# CW308_Mechanical.net
KiCad netlist of a schematic drawn in Altium Designer
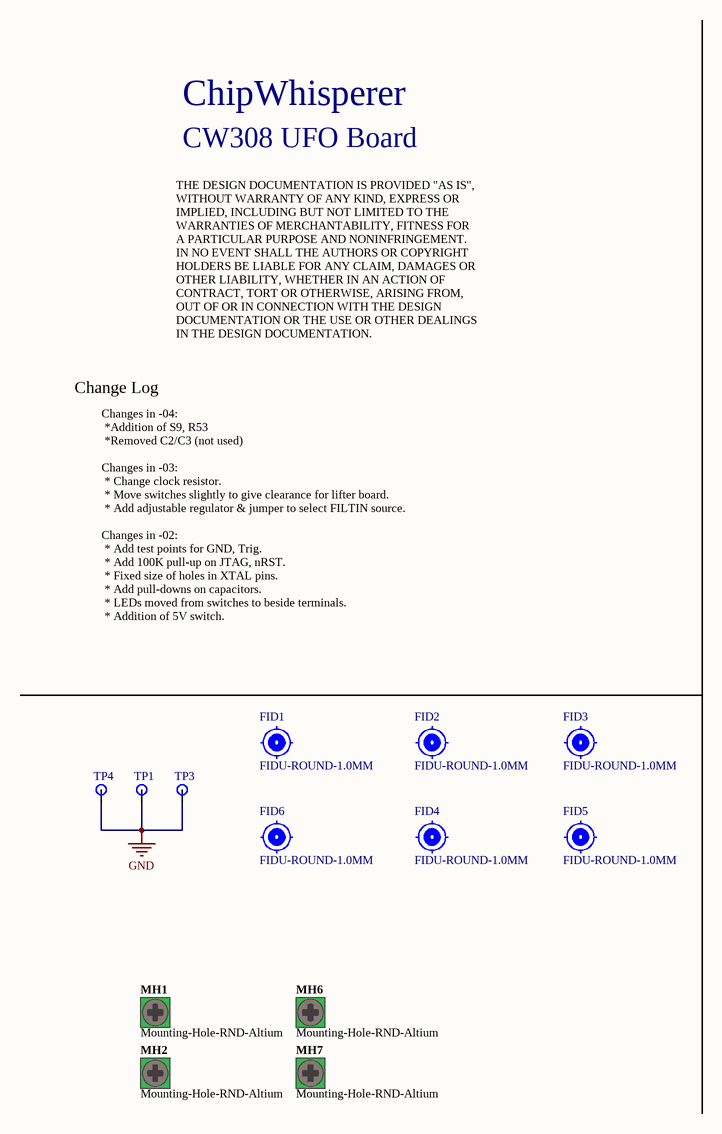
[diagram p0: CW308_Mechanical.SchDoc]

(export (version "E")
  (design (tool "Eeschema 10.0.6"))
  (components
    (comp (ref "FID1")
      (value "FIDU-ROUND-1.0MM")
      (footprint "FIDU-ROUND-1.0mm")
      (description "ROUND FIDUCIAL")
      (libsource (lib "NewAE_AltiumLib") (part "FIDU-ROUND-1.0MM"))
    )
    (comp (ref "FID2")
      (value "FIDU-ROUND-1.0MM")
      (footprint "FIDU-ROUND-1.0mm")
      (description "ROUND FIDUCIAL")
      (libsource (lib "NewAE_AltiumLib") (part "FIDU-ROUND-1.0MM"))
    )
    (comp (ref "FID3")
      (value "FIDU-ROUND-1.0MM")
      (footprint "FIDU-ROUND-1.0mm")
      (description "ROUND FIDUCIAL")
      (libsource (lib "NewAE_AltiumLib") (part "FIDU-ROUND-1.0MM"))
    )
    (comp (ref "FID4")
      (value "FIDU-ROUND-1.0MM")
      (footprint "FIDU-ROUND-1.0mm")
      (description "ROUND FIDUCIAL")
      (libsource (lib "NewAE_AltiumLib") (part "FIDU-ROUND-1.0MM"))
    )
    (comp (ref "FID5")
      (value "FIDU-ROUND-1.0MM")
      (footprint "FIDU-ROUND-1.0mm")
      (description "ROUND FIDUCIAL")
      (libsource (lib "NewAE_AltiumLib") (part "FIDU-ROUND-1.0MM"))
    )
    (comp (ref "FID6")
      (value "FIDU-ROUND-1.0MM")
      (footprint "FIDU-ROUND-1.0mm")
      (description "ROUND FIDUCIAL")
      (libsource (lib "NewAE_AltiumLib") (part "FIDU-ROUND-1.0MM"))
    )
    (comp (ref "MH1")
      (value "Mounting-Hole-RND-Altium")
      (footprint "Mounting-Hole-RND-Altium")
      (description "Mounting Hole, Altium, 4.4mm pad, 3.4mm plated hole")
      (fields (field (name "PUBLISHER") "Altium"))
      (libsource (lib "Altium Content Vault") (part "CMP-0001-00029-1"))
    )
    (comp (ref "MH2")
      (value "Mounting-Hole-RND-Altium")
      (footprint "Mounting-Hole-RND-Altium")
      (description "Mounting Hole, Altium, 4.4mm pad, 3.4mm plated hole")
      (fields (field (name "PUBLISHER") "Altium"))
      (libsource (lib "Altium Content Vault") (part "CMP-0001-00029-1"))
    )
    (comp (ref "MH6")
      (value "Mounting-Hole-RND-Altium")
      (footprint "Mounting-Hole-RND-Altium")
      (description "Mounting Hole, Altium, 4.4mm pad, 3.4mm plated hole")
      (fields (field (name "PUBLISHER") "Altium"))
      (libsource (lib "Altium Content Vault") (part "CMP-0001-00029-1"))
    )
    (comp (ref "MH7")
      (value "Mounting-Hole-RND-Altium")
      (footprint "Mounting-Hole-RND-Altium")
      (description "Mounting Hole, Altium, 4.4mm pad, 3.4mm plated hole")
      (fields (field (name "PUBLISHER") "Altium"))
      (libsource (lib "Altium Content Vault") (part "CMP-0001-00029-1"))
    )
    (comp (ref "TP1")
      (value "5011")
      (footprint "NewAE_AltiumLib:KEYSTONE5011")
      (description "TEST POINT PC MULTI PURPOSE BLK")
      (libsource (lib "NewAE_AltiumLib") (part "KEYSTONE_5011"))
    )
    (comp (ref "TP3")
      (value "5011")
      (footprint "NewAE_AltiumLib:KEYSTONE5011")
      (description "TEST POINT PC MULTI PURPOSE BLK")
      (libsource (lib "NewAE_AltiumLib") (part "KEYSTONE_5011"))
    )
    (comp (ref "TP4")
      (value "5011")
      (footprint "NewAE_AltiumLib:KEYSTONE5011")
      (description "TEST POINT PC MULTI PURPOSE BLK")
      (libsource (lib "NewAE_AltiumLib") (part "KEYSTONE_5011"))
    )
  )
  (nets
    (net (code "1") (name "GND") (class "Default")
      (node (ref "TP1") (pin "1") (pinfunction "1_1") (pintype "passive"))
      (node (ref "TP3") (pin "1") (pinfunction "1_1") (pintype "passive"))
      (node (ref "TP4") (pin "1") (pinfunction "1_1") (pintype "passive"))
    )
    (net (code "2") (name "unconnected-(MH1-Pad1)") (class "Default")
      (node (ref "MH1") (pin "1") (pinfunction "1_1") (pintype "passive"))
    )
    (net (code "3") (name "unconnected-(MH2-Pad1)") (class "Default")
      (node (ref "MH2") (pin "1") (pinfunction "1_1") (pintype "passive"))
    )
    (net (code "4") (name "unconnected-(MH6-Pad1)") (class "Default")
      (node (ref "MH6") (pin "1") (pinfunction "1_1") (pintype "passive"))
    )
    (net (code "5") (name "unconnected-(MH7-Pad1)") (class "Default")
      (node (ref "MH7") (pin "1") (pinfunction "1_1") (pintype "passive"))
    )
  )
)
